# FPGA.net
KiCad netlist of a schematic drawn in Altium Designer
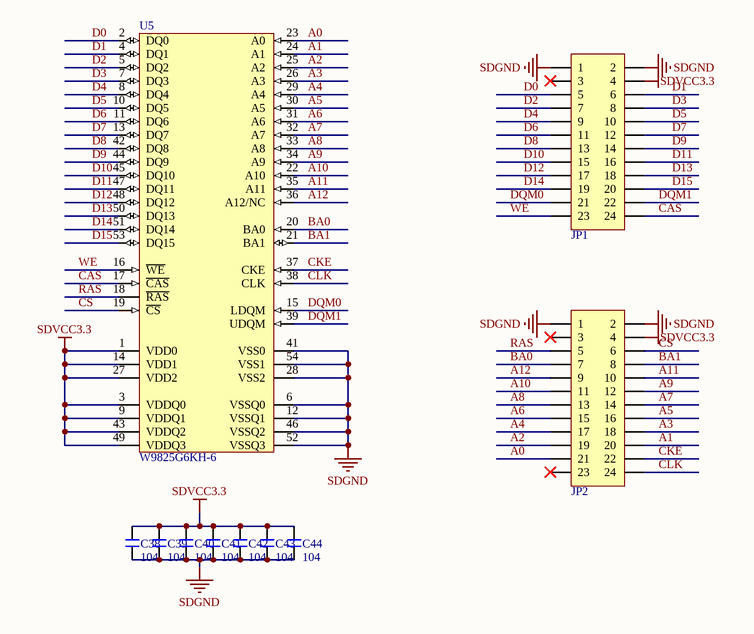
[diagram p0: FPGA扩展板.SchDoc]

(export (version "E")
  (design (tool "Eeschema 10.0.6"))
  (components
    (comp (ref "C38")
      (value "104")
      (footprint "C 0603_L")
      (description "贴片电容")
      (libsource (lib "0.1 - 电阻-电容-电感") (part "C"))
    )
    (comp (ref "C39")
      (value "104")
      (footprint "C 0603_L")
      (description "贴片电容")
      (libsource (lib "0.1 - 电阻-电容-电感") (part "C"))
    )
    (comp (ref "C40")
      (value "104")
      (footprint "C 0603_L")
      (description "贴片电容")
      (libsource (lib "0.1 - 电阻-电容-电感") (part "C"))
    )
    (comp (ref "C41")
      (value "104")
      (footprint "C 0603_L")
      (description "贴片电容")
      (libsource (lib "0.1 - 电阻-电容-电感") (part "C"))
    )
    (comp (ref "C42")
      (value "104")
      (footprint "C 0603_L")
      (description "贴片电容")
      (libsource (lib "0.1 - 电阻-电容-电感") (part "C"))
    )
    (comp (ref "C43")
      (value "104")
      (footprint "C 0603_L")
      (description "贴片电容")
      (libsource (lib "0.1 - 电阻-电容-电感") (part "C"))
    )
    (comp (ref "C44")
      (value "104")
      (footprint "C 0603_L")
      (description "贴片电容")
      (libsource (lib "0.1 - 电阻-电容-电感") (part "C"))
    )
    (comp (ref "JP1")
      (value "Header 2X11")
      (footprint "HDR2.54-LI-2x12P")
      (description "12*2P接插件")
      (fields (field (name "版权归属") "源创客"))
      (libsource (lib "5.3 - 接插件-脚距2.54 (100mil) ") (part "Header 12X2"))
    )
    (comp (ref "JP2")
      (value "Header 2X11")
      (footprint "HDR2.54-LI-2x12P")
      (description "12*2P接插件")
      (fields (field (name "版权归属") "源创客"))
      (libsource (lib "5.3 - 接插件-脚距2.54 (100mil) ") (part "Header 12X2"))
    )
    (comp (ref "U5")
      (value "W9825G6KH-6")
      (footprint "TSOP54")
      (description "32MB SDRAM")
      (libsource (lib "PIONEER") (part "IS42S16160B"))
    )
  )
  (nets
    (net (code "1") (name "/A0") (class "Default")
      (node (ref "JP2") (pin "21") (pinfunction "21_21") (pintype "passive"))
      (node (ref "U5") (pin "23") (pinfunction "A0_23") (pintype "input"))
    )
    (net (code "2") (name "/A1") (class "Default")
      (node (ref "JP2") (pin "20") (pinfunction "20_20") (pintype "passive"))
      (node (ref "U5") (pin "24") (pinfunction "A1_24") (pintype "input"))
    )
    (net (code "3") (name "/A2") (class "Default")
      (node (ref "JP2") (pin "19") (pinfunction "19_19") (pintype "passive"))
      (node (ref "U5") (pin "25") (pinfunction "A2_25") (pintype "input"))
    )
    (net (code "4") (name "/A3") (class "Default")
      (node (ref "JP2") (pin "18") (pinfunction "18_18") (pintype "passive"))
      (node (ref "U5") (pin "26") (pinfunction "A3_26") (pintype "input"))
    )
    (net (code "5") (name "/A4") (class "Default")
      (node (ref "JP2") (pin "17") (pinfunction "17_17") (pintype "passive"))
      (node (ref "U5") (pin "29") (pinfunction "A4_29") (pintype "input"))
    )
    (net (code "6") (name "/A5") (class "Default")
      (node (ref "JP2") (pin "16") (pinfunction "16_16") (pintype "passive"))
      (node (ref "U5") (pin "30") (pinfunction "A5_30") (pintype "input"))
    )
    (net (code "7") (name "/A6") (class "Default")
      (node (ref "JP2") (pin "15") (pinfunction "15_15") (pintype "passive"))
      (node (ref "U5") (pin "31") (pinfunction "A6_31") (pintype "input"))
    )
    (net (code "8") (name "/A7") (class "Default")
      (node (ref "JP2") (pin "14") (pinfunction "14_14") (pintype "passive"))
      (node (ref "U5") (pin "32") (pinfunction "A7_32") (pintype "input"))
    )
    (net (code "9") (name "/A8") (class "Default")
      (node (ref "JP2") (pin "13") (pinfunction "13_13") (pintype "passive"))
      (node (ref "U5") (pin "33") (pinfunction "A8_33") (pintype "input"))
    )
    (net (code "10") (name "/A9") (class "Default")
      (node (ref "JP2") (pin "12") (pinfunction "12_12") (pintype "passive"))
      (node (ref "U5") (pin "34") (pinfunction "A9_34") (pintype "input"))
    )
    (net (code "11") (name "/A10") (class "Default")
      (node (ref "JP2") (pin "11") (pinfunction "11_11") (pintype "passive"))
      (node (ref "U5") (pin "22") (pinfunction "A10_22") (pintype "input"))
    )
    (net (code "12") (name "/A11") (class "Default")
      (node (ref "JP2") (pin "10") (pinfunction "10_10") (pintype "passive"))
      (node (ref "U5") (pin "35") (pinfunction "A11_35") (pintype "input"))
    )
    (net (code "13") (name "/A12") (class "Default")
      (node (ref "JP2") (pin "9") (pinfunction "9_9") (pintype "passive"))
      (node (ref "U5") (pin "36") (pinfunction "A12/NC_36") (pintype "input"))
    )
    (net (code "14") (name "/BA0") (class "Default")
      (node (ref "JP2") (pin "7") (pinfunction "7_7") (pintype "passive"))
      (node (ref "U5") (pin "20") (pinfunction "BA0_20") (pintype "input"))
    )
    (net (code "15") (name "/BA1") (class "Default")
      (node (ref "JP2") (pin "8") (pinfunction "8_8") (pintype "passive"))
      (node (ref "U5") (pin "21") (pinfunction "BA1_21") (pintype "bidirectional"))
    )
    (net (code "16") (name "/CAS") (class "Default")
      (node (ref "JP1") (pin "24") (pinfunction "24_24") (pintype "passive"))
      (node (ref "U5") (pin "17") (pinfunction "~{CAS}_17") (pintype "input"))
    )
    (net (code "17") (name "/CKE") (class "Default")
      (node (ref "JP2") (pin "22") (pinfunction "22_22") (pintype "passive"))
      (node (ref "U5") (pin "37") (pinfunction "CKE_37") (pintype "input"))
    )
    (net (code "18") (name "/CLK") (class "Default")
      (node (ref "JP2") (pin "24") (pinfunction "24_24") (pintype "passive"))
      (node (ref "U5") (pin "38") (pinfunction "CLK_38") (pintype "input"))
    )
    (net (code "19") (name "/CS") (class "Default")
      (node (ref "JP2") (pin "6") (pinfunction "6_6") (pintype "passive"))
      (node (ref "U5") (pin "19") (pinfunction "~{CS}_19") (pintype "input"))
    )
    (net (code "20") (name "/D0") (class "Default")
      (node (ref "JP1") (pin "5") (pinfunction "5_5") (pintype "passive"))
      (node (ref "U5") (pin "2") (pinfunction "DQ0_2") (pintype "bidirectional"))
    )
    (net (code "21") (name "/D1") (class "Default")
      (node (ref "JP1") (pin "6") (pinfunction "6_6") (pintype "passive"))
      (node (ref "U5") (pin "4") (pinfunction "DQ1_4") (pintype "bidirectional"))
    )
    (net (code "22") (name "/D2") (class "Default")
      (node (ref "JP1") (pin "7") (pinfunction "7_7") (pintype "passive"))
      (node (ref "U5") (pin "5") (pinfunction "DQ2_5") (pintype "bidirectional"))
    )
    (net (code "23") (name "/D3") (class "Default")
      (node (ref "JP1") (pin "8") (pinfunction "8_8") (pintype "passive"))
      (node (ref "U5") (pin "7") (pinfunction "DQ3_7") (pintype "bidirectional"))
    )
    (net (code "24") (name "/D4") (class "Default")
      (node (ref "JP1") (pin "9") (pinfunction "9_9") (pintype "passive"))
      (node (ref "U5") (pin "8") (pinfunction "DQ4_8") (pintype "bidirectional"))
    )
    (net (code "25") (name "/D5") (class "Default")
      (node (ref "JP1") (pin "10") (pinfunction "10_10") (pintype "passive"))
      (node (ref "U5") (pin "10") (pinfunction "DQ5_10") (pintype "bidirectional"))
    )
    (net (code "26") (name "/D6") (class "Default")
      (node (ref "JP1") (pin "11") (pinfunction "11_11") (pintype "passive"))
      (node (ref "U5") (pin "11") (pinfunction "DQ6_11") (pintype "bidirectional"))
    )
    (net (code "27") (name "/D7") (class "Default")
      (node (ref "JP1") (pin "12") (pinfunction "12_12") (pintype "passive"))
      (node (ref "U5") (pin "13") (pinfunction "DQ7_13") (pintype "bidirectional"))
    )
    (net (code "28") (name "/D8") (class "Default")
      (node (ref "JP1") (pin "13") (pinfunction "13_13") (pintype "passive"))
      (node (ref "U5") (pin "42") (pinfunction "DQ8_42") (pintype "bidirectional"))
    )
    (net (code "29") (name "/D9") (class "Default")
      (node (ref "JP1") (pin "14") (pinfunction "14_14") (pintype "passive"))
      (node (ref "U5") (pin "44") (pinfunction "DQ9_44") (pintype "bidirectional"))
    )
    (net (code "30") (name "/D10") (class "Default")
      (node (ref "JP1") (pin "15") (pinfunction "15_15") (pintype "passive"))
      (node (ref "U5") (pin "45") (pinfunction "DQ10_45") (pintype "bidirectional"))
    )
    (net (code "31") (name "/D11") (class "Default")
      (node (ref "JP1") (pin "16") (pinfunction "16_16") (pintype "passive"))
      (node (ref "U5") (pin "47") (pinfunction "DQ11_47") (pintype "bidirectional"))
    )
    (net (code "32") (name "/D12") (class "Default")
      (node (ref "JP1") (pin "17") (pinfunction "17_17") (pintype "passive"))
      (node (ref "U5") (pin "48") (pinfunction "DQ12_48") (pintype "bidirectional"))
    )
    (net (code "33") (name "/D13") (class "Default")
      (node (ref "JP1") (pin "18") (pinfunction "18_18") (pintype "passive"))
      (node (ref "U5") (pin "50") (pinfunction "DQ13_50") (pintype "bidirectional"))
    )
    (net (code "34") (name "/D14") (class "Default")
      (node (ref "JP1") (pin "19") (pinfunction "19_19") (pintype "passive"))
      (node (ref "U5") (pin "51") (pinfunction "DQ14_51") (pintype "bidirectional"))
    )
    (net (code "35") (name "/D15") (class "Default")
      (node (ref "JP1") (pin "20") (pinfunction "20_20") (pintype "passive"))
      (node (ref "U5") (pin "53") (pinfunction "DQ15_53") (pintype "bidirectional"))
    )
    (net (code "36") (name "/DQM0") (class "Default")
      (node (ref "JP1") (pin "21") (pinfunction "21_21") (pintype "passive"))
      (node (ref "U5") (pin "15") (pinfunction "LDQM_15") (pintype "input"))
    )
    (net (code "37") (name "/DQM1") (class "Default")
      (node (ref "JP1") (pin "22") (pinfunction "22_22") (pintype "passive"))
      (node (ref "U5") (pin "39") (pinfunction "UDQM_39") (pintype "input"))
    )
    (net (code "38") (name "/RAS") (class "Default")
      (node (ref "JP2") (pin "5") (pinfunction "5_5") (pintype "passive"))
      (node (ref "U5") (pin "18") (pinfunction "~{RAS}_18") (pintype "passive"))
    )
    (net (code "39") (name "/WE") (class "Default")
      (node (ref "JP1") (pin "23") (pinfunction "23_23") (pintype "passive"))
      (node (ref "U5") (pin "16") (pinfunction "~{WE}_16") (pintype "input"))
    )
    (net (code "40") (name "SDGND") (class "Default")
      (node (ref "C38") (pin "1") (pinfunction "1_1") (pintype "passive"))
      (node (ref "C39") (pin "1") (pinfunction "1_1") (pintype "passive"))
      (node (ref "C40") (pin "1") (pinfunction "1_1") (pintype "passive"))
      (node (ref "C41") (pin "1") (pinfunction "1_1") (pintype "passive"))
      (node (ref "C42") (pin "1") (pinfunction "1_1") (pintype "passive"))
      (node (ref "C43") (pin "1") (pinfunction "1_1") (pintype "passive"))
      (node (ref "C44") (pin "1") (pinfunction "1_1") (pintype "passive"))
      (node (ref "JP1") (pin "1") (pinfunction "1_1") (pintype "passive"))
      (node (ref "JP1") (pin "2") (pinfunction "2_2") (pintype "passive"))
      (node (ref "JP2") (pin "1") (pinfunction "1_1") (pintype "passive"))
      (node (ref "JP2") (pin "2") (pinfunction "2_2") (pintype "passive"))
      (node (ref "U5") (pin "12") (pinfunction "VSSQ1_12") (pintype "power_in"))
      (node (ref "U5") (pin "28") (pinfunction "VSS2_28") (pintype "power_in"))
      (node (ref "U5") (pin "41") (pinfunction "VSS0_41") (pintype "power_in"))
      (node (ref "U5") (pin "46") (pinfunction "VSSQ2_46") (pintype "power_in"))
      (node (ref "U5") (pin "52") (pinfunction "VSSQ3_52") (pintype "power_in"))
      (node (ref "U5") (pin "54") (pinfunction "VSS1_54") (pintype "power_in"))
      (node (ref "U5") (pin "6") (pinfunction "VSSQ0_6") (pintype "power_in"))
    )
    (net (code "41") (name "SDVCC3.3") (class "Default")
      (node (ref "C38") (pin "2") (pinfunction "2_2") (pintype "passive"))
      (node (ref "C39") (pin "2") (pinfunction "2_2") (pintype "passive"))
      (node (ref "C40") (pin "2") (pinfunction "2_2") (pintype "passive"))
      (node (ref "C41") (pin "2") (pinfunction "2_2") (pintype "passive"))
      (node (ref "C42") (pin "2") (pinfunction "2_2") (pintype "passive"))
      (node (ref "C43") (pin "2") (pinfunction "2_2") (pintype "passive"))
      (node (ref "C44") (pin "2") (pinfunction "2_2") (pintype "passive"))
      (node (ref "JP1") (pin "4") (pinfunction "4_4") (pintype "passive"))
      (node (ref "JP2") (pin "4") (pinfunction "4_4") (pintype "passive"))
      (node (ref "U5") (pin "1") (pinfunction "VDD0_1") (pintype "power_in"))
      (node (ref "U5") (pin "14") (pinfunction "VDD1_14") (pintype "power_in"))
      (node (ref "U5") (pin "27") (pinfunction "VDD2_27") (pintype "power_in"))
      (node (ref "U5") (pin "3") (pinfunction "VDDQ0_3") (pintype "power_in"))
      (node (ref "U5") (pin "43") (pinfunction "VDDQ2_43") (pintype "power_in"))
      (node (ref "U5") (pin "49") (pinfunction "VDDQ3_49") (pintype "power_in"))
      (node (ref "U5") (pin "9") (pinfunction "VDDQ1_9") (pintype "power_in"))
    )
    (net (code "42") (name "unconnected-(JP1-Pad3)") (class "Default")
      (node (ref "JP1") (pin "3") (pinfunction "3_3") (pintype "passive+no_connect"))
    )
    (net (code "43") (name "unconnected-(JP2-Pad3)") (class "Default")
      (node (ref "JP2") (pin "3") (pinfunction "3_3") (pintype "passive+no_connect"))
    )
    (net (code "44") (name "unconnected-(JP2-Pad23)") (class "Default")
      (node (ref "JP2") (pin "23") (pinfunction "23_23") (pintype "passive+no_connect"))
    )
  )
)
